# 6_cpu_registers_b.net
KiCad netlist of a schematic drawn in EAGLE
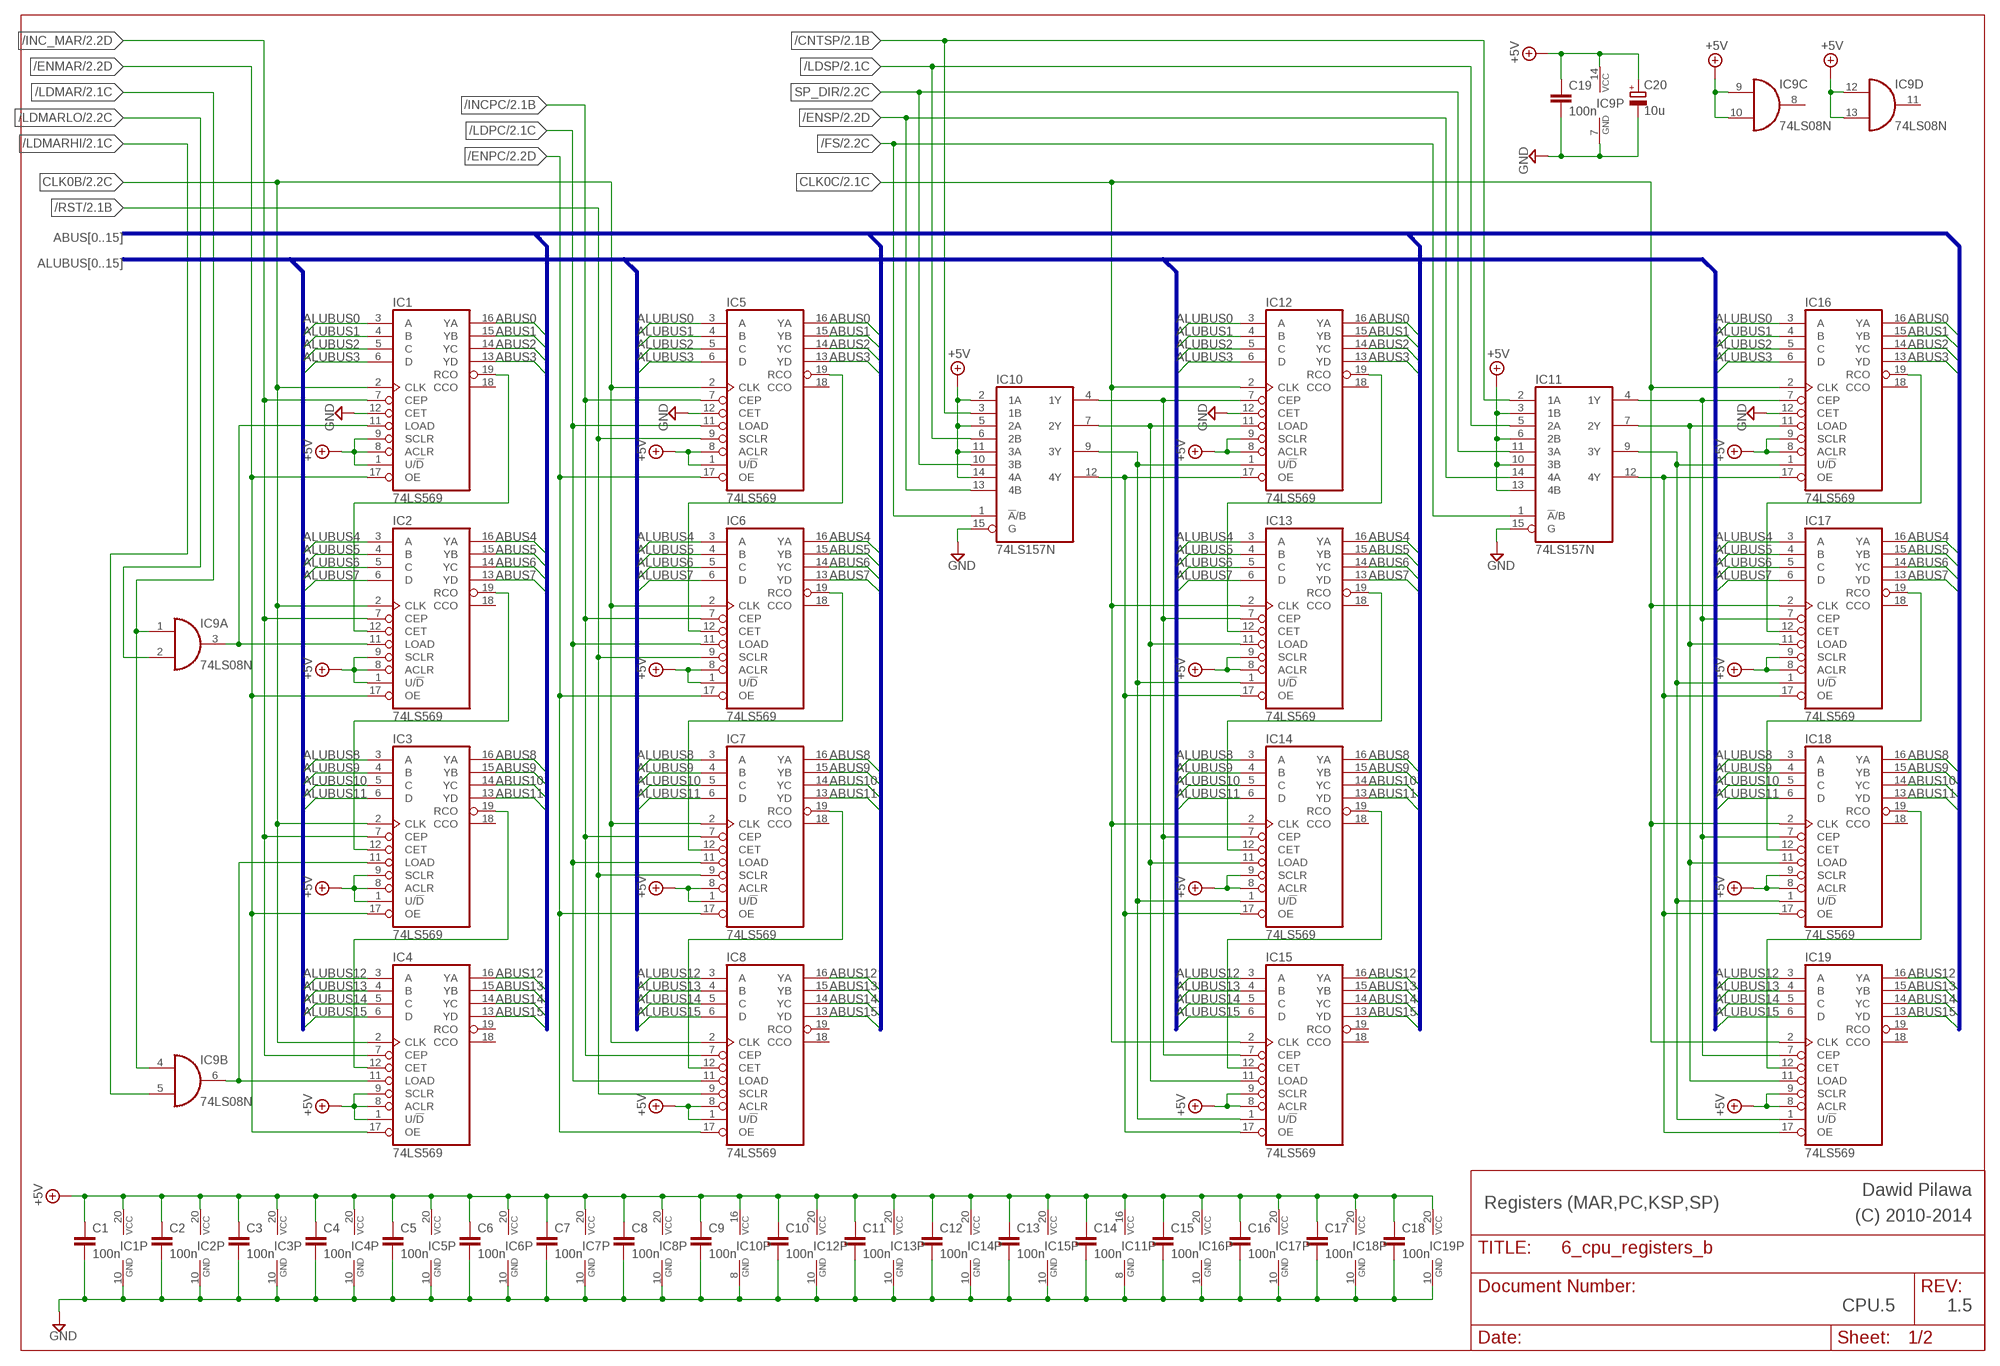
[diagram p0: schematic, sheet 1]
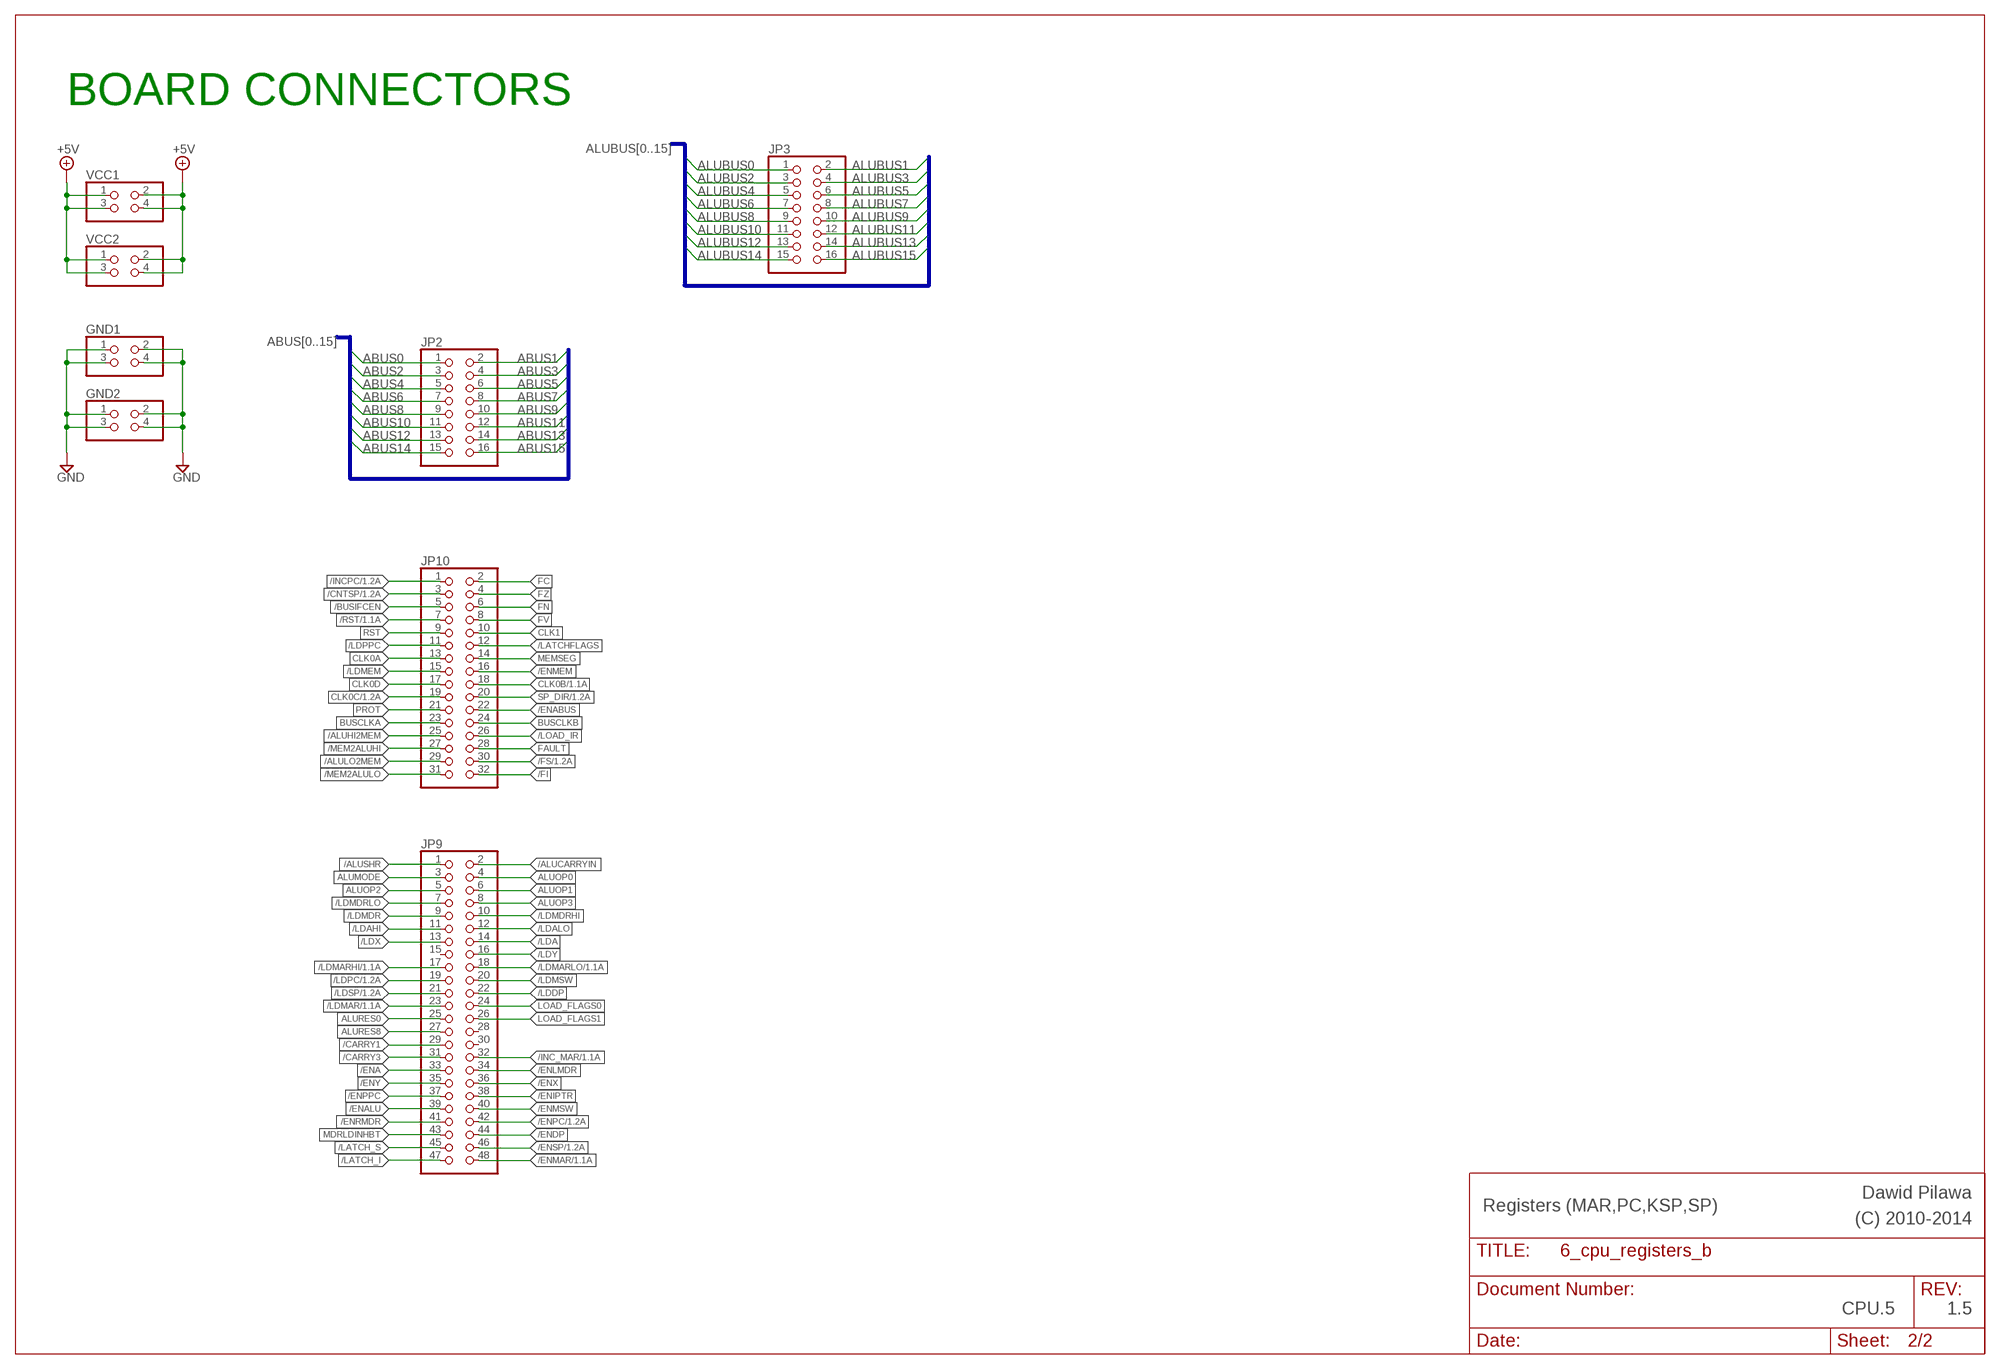
[diagram p1: schematic, sheet 2]

(export (version "E")
  (design (tool "Eeschema 10.0.6"))
  (components
    (comp (ref "GND1")
      (value "PINHD-2X2")
      (footprint "eagle-import:2X02")
      (libsource (lib "eagle-import") (part "PINHD-2X2"))
    )
    (comp (ref "GND2")
      (value "PINHD-2X2")
      (footprint "eagle-import:2X02")
      (libsource (lib "eagle-import") (part "PINHD-2X2"))
    )
    (comp (ref "JP2")
      (value "PINHD-2X8")
      (footprint "eagle-import:2X08")
      (libsource (lib "eagle-import") (part "PINHD-2X8"))
    )
    (comp (ref "JP3")
      (value "PINHD-2X8")
      (footprint "eagle-import:2X08")
      (libsource (lib "eagle-import") (part "PINHD-2X8"))
    )
    (comp (ref "JP9")
      (value "PINHD-2X24")
      (footprint "eagle-import:2X24")
      (libsource (lib "eagle-import") (part "PINHD-2X24"))
    )
    (comp (ref "JP10")
      (value "PINHD-2X16")
      (footprint "eagle-import:2X16")
      (libsource (lib "eagle-import") (part "PINHD-2X16"))
    )
    (comp (ref "VCC1")
      (value "PINHD-2X2")
      (footprint "eagle-import:2X02")
      (libsource (lib "eagle-import") (part "PINHD-2X2"))
    )
    (comp (ref "VCC2")
      (value "PINHD-2X2")
      (footprint "eagle-import:2X02")
      (libsource (lib "eagle-import") (part "PINHD-2X2"))
    )
    (comp (ref "C1")
      (value "100n")
      (footprint "eagle-import:C050-024X044")
      (libsource (lib "eagle-import") (part "C-EU050-024X044"))
    )
    (comp (ref "C2")
      (value "100n")
      (footprint "eagle-import:C050-024X044")
      (libsource (lib "eagle-import") (part "C-EU050-024X044"))
    )
    (comp (ref "C3")
      (value "100n")
      (footprint "eagle-import:C050-024X044")
      (libsource (lib "eagle-import") (part "C-EU050-024X044"))
    )
    (comp (ref "C4")
      (value "100n")
      (footprint "eagle-import:C050-024X044")
      (libsource (lib "eagle-import") (part "C-EU050-024X044"))
    )
    (comp (ref "C5")
      (value "100n")
      (footprint "eagle-import:C050-024X044")
      (libsource (lib "eagle-import") (part "C-EU050-024X044"))
    )
    (comp (ref "C6")
      (value "100n")
      (footprint "eagle-import:C050-024X044")
      (libsource (lib "eagle-import") (part "C-EU050-024X044"))
    )
    (comp (ref "C7")
      (value "100n")
      (footprint "eagle-import:C050-024X044")
      (libsource (lib "eagle-import") (part "C-EU050-024X044"))
    )
    (comp (ref "C8")
      (value "100n")
      (footprint "eagle-import:C050-024X044")
      (libsource (lib "eagle-import") (part "C-EU050-024X044"))
    )
    (comp (ref "C9")
      (value "100n")
      (footprint "eagle-import:C050-024X044")
      (libsource (lib "eagle-import") (part "C-EU050-024X044"))
    )
    (comp (ref "C10")
      (value "100n")
      (footprint "eagle-import:C050-024X044")
      (libsource (lib "eagle-import") (part "C-EU050-024X044"))
    )
    (comp (ref "C11")
      (value "100n")
      (footprint "eagle-import:C050-024X044")
      (libsource (lib "eagle-import") (part "C-EU050-024X044"))
    )
    (comp (ref "C12")
      (value "100n")
      (footprint "eagle-import:C050-024X044")
      (libsource (lib "eagle-import") (part "C-EU050-024X044"))
    )
    (comp (ref "C13")
      (value "100n")
      (footprint "eagle-import:C050-024X044")
      (libsource (lib "eagle-import") (part "C-EU050-024X044"))
    )
    (comp (ref "C14")
      (value "100n")
      (footprint "eagle-import:C050-024X044")
      (libsource (lib "eagle-import") (part "C-EU050-024X044"))
    )
    (comp (ref "C15")
      (value "100n")
      (footprint "eagle-import:C050-024X044")
      (libsource (lib "eagle-import") (part "C-EU050-024X044"))
    )
    (comp (ref "C16")
      (value "100n")
      (footprint "eagle-import:C050-024X044")
      (libsource (lib "eagle-import") (part "C-EU050-024X044"))
    )
    (comp (ref "C17")
      (value "100n")
      (footprint "eagle-import:C050-024X044")
      (libsource (lib "eagle-import") (part "C-EU050-024X044"))
    )
    (comp (ref "C18")
      (value "100n")
      (footprint "eagle-import:C050-024X044")
      (libsource (lib "eagle-import") (part "C-EU050-024X044"))
    )
    (comp (ref "C19")
      (value "100n")
      (footprint "eagle-import:C050-024X044")
      (libsource (lib "eagle-import") (part "C-EU050-024X044"))
    )
    (comp (ref "C20")
      (value "10u")
      (footprint "eagle-import:E2,5-6")
      (libsource (lib "eagle-import") (part "CPOL-EUE2.5-6"))
    )
    (comp (ref "IC1")
      (value "74LS569")
      (footprint "eagle-import:DIL20")
      (libsource (lib "eagle-import") (part "74569LS"))
    )
    (comp (ref "IC2")
      (value "74LS569")
      (footprint "eagle-import:DIL20")
      (libsource (lib "eagle-import") (part "74569LS"))
    )
    (comp (ref "IC3")
      (value "74LS569")
      (footprint "eagle-import:DIL20")
      (libsource (lib "eagle-import") (part "74569LS"))
    )
    (comp (ref "IC4")
      (value "74LS569")
      (footprint "eagle-import:DIL20")
      (libsource (lib "eagle-import") (part "74569LS"))
    )
    (comp (ref "IC5")
      (value "74LS569")
      (footprint "eagle-import:DIL20")
      (libsource (lib "eagle-import") (part "74569LS"))
    )
    (comp (ref "IC6")
      (value "74LS569")
      (footprint "eagle-import:DIL20")
      (libsource (lib "eagle-import") (part "74569LS"))
    )
    (comp (ref "IC7")
      (value "74LS569")
      (footprint "eagle-import:DIL20")
      (libsource (lib "eagle-import") (part "74569LS"))
    )
    (comp (ref "IC8")
      (value "74LS569")
      (footprint "eagle-import:DIL20")
      (libsource (lib "eagle-import") (part "74569LS"))
    )
    (comp (ref "IC9")
      (value "74LS08N")
      (footprint "eagle-import:DIL14")
      (libsource (lib "eagle-import") (part "7408NLS"))
    )
    (comp (ref "IC10")
      (value "74LS157N")
      (footprint "eagle-import:DIL16")
      (libsource (lib "eagle-import") (part "74157NLS"))
    )
    (comp (ref "IC11")
      (value "74LS157N")
      (footprint "eagle-import:DIL16")
      (libsource (lib "eagle-import") (part "74157NLS"))
    )
    (comp (ref "IC12")
      (value "74LS569")
      (footprint "eagle-import:DIL20")
      (libsource (lib "eagle-import") (part "74569LS"))
    )
    (comp (ref "IC13")
      (value "74LS569")
      (footprint "eagle-import:DIL20")
      (libsource (lib "eagle-import") (part "74569LS"))
    )
    (comp (ref "IC14")
      (value "74LS569")
      (footprint "eagle-import:DIL20")
      (libsource (lib "eagle-import") (part "74569LS"))
    )
    (comp (ref "IC15")
      (value "74LS569")
      (footprint "eagle-import:DIL20")
      (libsource (lib "eagle-import") (part "74569LS"))
    )
    (comp (ref "IC16")
      (value "74LS569")
      (footprint "eagle-import:DIL20")
      (libsource (lib "eagle-import") (part "74569LS"))
    )
    (comp (ref "IC17")
      (value "74LS569")
      (footprint "eagle-import:DIL20")
      (libsource (lib "eagle-import") (part "74569LS"))
    )
    (comp (ref "IC18")
      (value "74LS569")
      (footprint "eagle-import:DIL20")
      (libsource (lib "eagle-import") (part "74569LS"))
    )
    (comp (ref "IC19")
      (value "74LS569")
      (footprint "eagle-import:DIL20")
      (libsource (lib "eagle-import") (part "74569LS"))
    )
  )
  (nets
    (net (code "1") (name "+5V") (class "Default")
      (node (ref "C1") (pin "1") (pinfunction "1_1") (pintype "passive"))
      (node (ref "C10") (pin "1") (pinfunction "1_1") (pintype "passive"))
      (node (ref "C11") (pin "1") (pinfunction "1_1") (pintype "passive"))
      (node (ref "C12") (pin "1") (pinfunction "1_1") (pintype "passive"))
      (node (ref "C13") (pin "1") (pinfunction "1_1") (pintype "passive"))
      (node (ref "C14") (pin "1") (pinfunction "1_1") (pintype "passive"))
      (node (ref "C15") (pin "1") (pinfunction "1_1") (pintype "passive"))
      (node (ref "C16") (pin "1") (pinfunction "1_1") (pintype "passive"))
      (node (ref "C17") (pin "1") (pinfunction "1_1") (pintype "passive"))
      (node (ref "C18") (pin "1") (pinfunction "1_1") (pintype "passive"))
      (node (ref "C19") (pin "1") (pinfunction "1_1") (pintype "passive"))
      (node (ref "C2") (pin "1") (pinfunction "1_1") (pintype "passive"))
      (node (ref "C20") (pin "+") (pinfunction "+_+") (pintype "passive"))
      (node (ref "C3") (pin "1") (pinfunction "1_1") (pintype "passive"))
      (node (ref "C4") (pin "1") (pinfunction "1_1") (pintype "passive"))
      (node (ref "C5") (pin "1") (pinfunction "1_1") (pintype "passive"))
      (node (ref "C6") (pin "1") (pinfunction "1_1") (pintype "passive"))
      (node (ref "C7") (pin "1") (pinfunction "1_1") (pintype "passive"))
      (node (ref "C8") (pin "1") (pinfunction "1_1") (pintype "passive"))
      (node (ref "C9") (pin "1") (pinfunction "1_1") (pintype "passive"))
      (node (ref "IC1") (pin "1") (pinfunction "U/~{D}_1") (pintype "input"))
      (node (ref "IC1") (pin "20") (pinfunction "VCC_20") (pintype "power_in"))
      (node (ref "IC1") (pin "8") (pinfunction "ACLR_8") (pintype "input"))
      (node (ref "IC1") (pin "9") (pinfunction "SCLR_9") (pintype "input"))
      (node (ref "IC10") (pin "11") (pinfunction "3A_11") (pintype "input"))
      (node (ref "IC10") (pin "14") (pinfunction "4A_14") (pintype "input"))
      (node (ref "IC10") (pin "16") (pinfunction "VCC_16") (pintype "power_in"))
      (node (ref "IC10") (pin "2") (pinfunction "1A_2") (pintype "input"))
      (node (ref "IC10") (pin "5") (pinfunction "2A_5") (pintype "input"))
      (node (ref "IC11") (pin "10") (pinfunction "3B_10") (pintype "input"))
      (node (ref "IC11") (pin "13") (pinfunction "4B_13") (pintype "input"))
      (node (ref "IC11") (pin "16") (pinfunction "VCC_16") (pintype "power_in"))
      (node (ref "IC11") (pin "3") (pinfunction "1B_3") (pintype "input"))
      (node (ref "IC11") (pin "6") (pinfunction "2B_6") (pintype "input"))
      (node (ref "IC12") (pin "20") (pinfunction "VCC_20") (pintype "power_in"))
      (node (ref "IC12") (pin "8") (pinfunction "ACLR_8") (pintype "input"))
      (node (ref "IC12") (pin "9") (pinfunction "SCLR_9") (pintype "input"))
      (node (ref "IC13") (pin "20") (pinfunction "VCC_20") (pintype "power_in"))
      (node (ref "IC13") (pin "8") (pinfunction "ACLR_8") (pintype "input"))
      (node (ref "IC13") (pin "9") (pinfunction "SCLR_9") (pintype "input"))
      (node (ref "IC14") (pin "20") (pinfunction "VCC_20") (pintype "power_in"))
      (node (ref "IC14") (pin "8") (pinfunction "ACLR_8") (pintype "input"))
      (node (ref "IC14") (pin "9") (pinfunction "SCLR_9") (pintype "input"))
      (node (ref "IC15") (pin "20") (pinfunction "VCC_20") (pintype "power_in"))
      (node (ref "IC15") (pin "8") (pinfunction "ACLR_8") (pintype "input"))
      (node (ref "IC15") (pin "9") (pinfunction "SCLR_9") (pintype "input"))
      (node (ref "IC16") (pin "20") (pinfunction "VCC_20") (pintype "power_in"))
      (node (ref "IC16") (pin "8") (pinfunction "ACLR_8") (pintype "input"))
      (node (ref "IC16") (pin "9") (pinfunction "SCLR_9") (pintype "input"))
      (node (ref "IC17") (pin "20") (pinfunction "VCC_20") (pintype "power_in"))
      (node (ref "IC17") (pin "8") (pinfunction "ACLR_8") (pintype "input"))
      (node (ref "IC17") (pin "9") (pinfunction "SCLR_9") (pintype "input"))
      (node (ref "IC18") (pin "20") (pinfunction "VCC_20") (pintype "power_in"))
      (node (ref "IC18") (pin "8") (pinfunction "ACLR_8") (pintype "input"))
      (node (ref "IC18") (pin "9") (pinfunction "SCLR_9") (pintype "input"))
      (node (ref "IC19") (pin "20") (pinfunction "VCC_20") (pintype "power_in"))
      (node (ref "IC19") (pin "8") (pinfunction "ACLR_8") (pintype "input"))
      (node (ref "IC19") (pin "9") (pinfunction "SCLR_9") (pintype "input"))
      (node (ref "IC2") (pin "1") (pinfunction "U/~{D}_1") (pintype "input"))
      (node (ref "IC2") (pin "20") (pinfunction "VCC_20") (pintype "power_in"))
      (node (ref "IC2") (pin "8") (pinfunction "ACLR_8") (pintype "input"))
      (node (ref "IC2") (pin "9") (pinfunction "SCLR_9") (pintype "input"))
      (node (ref "IC3") (pin "1") (pinfunction "U/~{D}_1") (pintype "input"))
      (node (ref "IC3") (pin "20") (pinfunction "VCC_20") (pintype "power_in"))
      (node (ref "IC3") (pin "8") (pinfunction "ACLR_8") (pintype "input"))
      (node (ref "IC3") (pin "9") (pinfunction "SCLR_9") (pintype "input"))
      (node (ref "IC4") (pin "1") (pinfunction "U/~{D}_1") (pintype "input"))
      (node (ref "IC4") (pin "20") (pinfunction "VCC_20") (pintype "power_in"))
      (node (ref "IC4") (pin "8") (pinfunction "ACLR_8") (pintype "input"))
      (node (ref "IC4") (pin "9") (pinfunction "SCLR_9") (pintype "input"))
      (node (ref "IC5") (pin "1") (pinfunction "U/~{D}_1") (pintype "input"))
      (node (ref "IC5") (pin "20") (pinfunction "VCC_20") (pintype "power_in"))
      (node (ref "IC5") (pin "8") (pinfunction "ACLR_8") (pintype "input"))
      (node (ref "IC6") (pin "1") (pinfunction "U/~{D}_1") (pintype "input"))
      (node (ref "IC6") (pin "20") (pinfunction "VCC_20") (pintype "power_in"))
      (node (ref "IC6") (pin "8") (pinfunction "ACLR_8") (pintype "input"))
      (node (ref "IC7") (pin "1") (pinfunction "U/~{D}_1") (pintype "input"))
      (node (ref "IC7") (pin "20") (pinfunction "VCC_20") (pintype "power_in"))
      (node (ref "IC7") (pin "8") (pinfunction "ACLR_8") (pintype "input"))
      (node (ref "IC8") (pin "1") (pinfunction "U/~{D}_1") (pintype "input"))
      (node (ref "IC8") (pin "20") (pinfunction "VCC_20") (pintype "power_in"))
      (node (ref "IC8") (pin "8") (pinfunction "ACLR_8") (pintype "input"))
      (node (ref "IC9") (pin "10") (pinfunction "I1_10") (pintype "input"))
      (node (ref "IC9") (pin "12") (pinfunction "I0_12") (pintype "input"))
      (node (ref "IC9") (pin "13") (pinfunction "I1_13") (pintype "input"))
      (node (ref "IC9") (pin "14") (pinfunction "VCC_14") (pintype "power_in"))
      (node (ref "IC9") (pin "9") (pinfunction "I0_9") (pintype "input"))
      (node (ref "VCC1") (pin "1") (pinfunction "1_1") (pintype "passive"))
      (node (ref "VCC1") (pin "2") (pinfunction "2_2") (pintype "passive"))
      (node (ref "VCC1") (pin "3") (pinfunction "3_3") (pintype "passive"))
      (node (ref "VCC1") (pin "4") (pinfunction "4_4") (pintype "passive"))
      (node (ref "VCC2") (pin "1") (pinfunction "1_1") (pintype "passive"))
      (node (ref "VCC2") (pin "2") (pinfunction "2_2") (pintype "passive"))
      (node (ref "VCC2") (pin "3") (pinfunction "3_3") (pintype "passive"))
      (node (ref "VCC2") (pin "4") (pinfunction "4_4") (pintype "passive"))
    )
    (net (code "6") (name "ABUS0") (class "Default")
      (node (ref "IC1") (pin "16") (pinfunction "YA_16") (pintype "open_collector"))
      (node (ref "IC12") (pin "16") (pinfunction "YA_16") (pintype "open_collector"))
      (node (ref "IC16") (pin "16") (pinfunction "YA_16") (pintype "open_collector"))
      (node (ref "IC5") (pin "16") (pinfunction "YA_16") (pintype "open_collector"))
      (node (ref "JP2") (pin "1") (pinfunction "1_1") (pintype "passive"))
    )
    (net (code "7") (name "ABUS1") (class "Default")
      (node (ref "IC1") (pin "15") (pinfunction "YB_15") (pintype "open_collector"))
      (node (ref "IC12") (pin "15") (pinfunction "YB_15") (pintype "open_collector"))
      (node (ref "IC16") (pin "15") (pinfunction "YB_15") (pintype "open_collector"))
      (node (ref "IC5") (pin "15") (pinfunction "YB_15") (pintype "open_collector"))
      (node (ref "JP2") (pin "2") (pinfunction "2_2") (pintype "passive"))
    )
    (net (code "8") (name "ABUS2") (class "Default")
      (node (ref "IC1") (pin "14") (pinfunction "YC_14") (pintype "open_collector"))
      (node (ref "IC12") (pin "14") (pinfunction "YC_14") (pintype "open_collector"))
      (node (ref "IC16") (pin "14") (pinfunction "YC_14") (pintype "open_collector"))
      (node (ref "IC5") (pin "14") (pinfunction "YC_14") (pintype "open_collector"))
      (node (ref "JP2") (pin "3") (pinfunction "3_3") (pintype "passive"))
    )
    (net (code "9") (name "ABUS3") (class "Default")
      (node (ref "IC1") (pin "13") (pinfunction "YD_13") (pintype "open_collector"))
      (node (ref "IC12") (pin "13") (pinfunction "YD_13") (pintype "open_collector"))
      (node (ref "IC16") (pin "13") (pinfunction "YD_13") (pintype "open_collector"))
      (node (ref "IC5") (pin "13") (pinfunction "YD_13") (pintype "open_collector"))
      (node (ref "JP2") (pin "4") (pinfunction "4_4") (pintype "passive"))
    )
    (net (code "10") (name "ABUS4") (class "Default")
      (node (ref "IC13") (pin "16") (pinfunction "YA_16") (pintype "open_collector"))
      (node (ref "IC17") (pin "16") (pinfunction "YA_16") (pintype "open_collector"))
      (node (ref "IC2") (pin "16") (pinfunction "YA_16") (pintype "open_collector"))
      (node (ref "IC6") (pin "16") (pinfunction "YA_16") (pintype "open_collector"))
      (node (ref "JP2") (pin "5") (pinfunction "5_5") (pintype "passive"))
    )
    (net (code "11") (name "ABUS5") (class "Default")
      (node (ref "IC13") (pin "15") (pinfunction "YB_15") (pintype "open_collector"))
      (node (ref "IC17") (pin "15") (pinfunction "YB_15") (pintype "open_collector"))
      (node (ref "IC2") (pin "15") (pinfunction "YB_15") (pintype "open_collector"))
      (node (ref "IC6") (pin "15") (pinfunction "YB_15") (pintype "open_collector"))
      (node (ref "JP2") (pin "6") (pinfunction "6_6") (pintype "passive"))
    )
    (net (code "12") (name "ABUS6") (class "Default")
      (node (ref "IC13") (pin "14") (pinfunction "YC_14") (pintype "open_collector"))
      (node (ref "IC17") (pin "14") (pinfunction "YC_14") (pintype "open_collector"))
      (node (ref "IC2") (pin "14") (pinfunction "YC_14") (pintype "open_collector"))
      (node (ref "IC6") (pin "14") (pinfunction "YC_14") (pintype "open_collector"))
      (node (ref "JP2") (pin "7") (pinfunction "7_7") (pintype "passive"))
    )
    (net (code "13") (name "ABUS7") (class "Default")
      (node (ref "IC13") (pin "13") (pinfunction "YD_13") (pintype "open_collector"))
      (node (ref "IC17") (pin "13") (pinfunction "YD_13") (pintype "open_collector"))
      (node (ref "IC2") (pin "13") (pinfunction "YD_13") (pintype "open_collector"))
      (node (ref "IC6") (pin "13") (pinfunction "YD_13") (pintype "open_collector"))
      (node (ref "JP2") (pin "8") (pinfunction "8_8") (pintype "passive"))
    )
    (net (code "14") (name "ABUS8") (class "Default")
      (node (ref "IC14") (pin "16") (pinfunction "YA_16") (pintype "open_collector"))
      (node (ref "IC18") (pin "16") (pinfunction "YA_16") (pintype "open_collector"))
      (node (ref "IC3") (pin "16") (pinfunction "YA_16") (pintype "open_collector"))
      (node (ref "IC7") (pin "16") (pinfunction "YA_16") (pintype "open_collector"))
      (node (ref "JP2") (pin "9") (pinfunction "9_9") (pintype "passive"))
    )
    (net (code "15") (name "ABUS9") (class "Default")
      (node (ref "IC14") (pin "15") (pinfunction "YB_15") (pintype "open_collector"))
      (node (ref "IC18") (pin "15") (pinfunction "YB_15") (pintype "open_collector"))
      (node (ref "IC3") (pin "15") (pinfunction "YB_15") (pintype "open_collector"))
      (node (ref "IC7") (pin "15") (pinfunction "YB_15") (pintype "open_collector"))
      (node (ref "JP2") (pin "10") (pinfunction "10_10") (pintype "passive"))
    )
    (net (code "16") (name "ABUS10") (class "Default")
      (node (ref "IC14") (pin "14") (pinfunction "YC_14") (pintype "open_collector"))
      (node (ref "IC18") (pin "14") (pinfunction "YC_14") (pintype "open_collector"))
      (node (ref "IC3") (pin "14") (pinfunction "YC_14") (pintype "open_collector"))
      (node (ref "IC7") (pin "14") (pinfunction "YC_14") (pintype "open_collector"))
      (node (ref "JP2") (pin "11") (pinfunction "11_11") (pintype "passive"))
    )
    (net (code "17") (name "ABUS11") (class "Default")
      (node (ref "IC14") (pin "13") (pinfunction "YD_13") (pintype "open_collector"))
      (node (ref "IC18") (pin "13") (pinfunction "YD_13") (pintype "open_collector"))
      (node (ref "IC3") (pin "13") (pinfunction "YD_13") (pintype "open_collector"))
      (node (ref "IC7") (pin "13") (pinfunction "YD_13") (pintype "open_collector"))
      (node (ref "JP2") (pin "12") (pinfunction "12_12") (pintype "passive"))
    )
    (net (code "18") (name "ABUS12") (class "Default")
      (node (ref "IC15") (pin "16") (pinfunction "YA_16") (pintype "open_collector"))
      (node (ref "IC19") (pin "16") (pinfunction "YA_16") (pintype "open_collector"))
      (node (ref "IC4") (pin "16") (pinfunction "YA_16") (pintype "open_collector"))
      (node (ref "IC8") (pin "16") (pinfunction "YA_16") (pintype "open_collector"))
      (node (ref "JP2") (pin "13") (pinfunction "13_13") (pintype "passive"))
    )
    (net (code "19") (name "ABUS13") (class "Default")
      (node (ref "IC15") (pin "15") (pinfunction "YB_15") (pintype "open_collector"))
      (node (ref "IC19") (pin "15") (pinfunction "YB_15") (pintype "open_collector"))
      (node (ref "IC4") (pin "15") (pinfunction "YB_15") (pintype "open_collector"))
      (node (ref "IC8") (pin "15") (pinfunction "YB_15") (pintype "open_collector"))
      (node (ref "JP2") (pin "14") (pinfunction "14_14") (pintype "passive"))
    )
    (net (code "20") (name "ABUS14") (class "Default")
      (node (ref "IC15") (pin "14") (pinfunction "YC_14") (pintype "open_collector"))
      (node (ref "IC19") (pin "14") (pinfunction "YC_14") (pintype "open_collector"))
      (node (ref "IC4") (pin "14") (pinfunction "YC_14") (pintype "open_collector"))
      (node (ref "IC8") (pin "14") (pinfunction "YC_14") (pintype "open_collector"))
      (node (ref "JP2") (pin "15") (pinfunction "15_15") (pintype "passive"))
    )
    (net (code "21") (name "ABUS15") (class "Default")
      (node (ref "IC15") (pin "13") (pinfunction "YD_13") (pintype "open_collector"))
      (node (ref "IC19") (pin "13") (pinfunction "YD_13") (pintype "open_collector"))
      (node (ref "IC4") (pin "13") (pinfunction "YD_13") (pintype "open_collector"))
      (node (ref "IC8") (pin "13") (pinfunction "YD_13") (pintype "open_collector"))
      (node (ref "JP2") (pin "16") (pinfunction "16_16") (pintype "passive"))
    )
    (net (code "22") (name "ALUBUS0") (class "Default")
      (node (ref "IC1") (pin "3") (pinfunction "A_3") (pintype "input"))
      (node (ref "IC12") (pin "3") (pinfunction "A_3") (pintype "input"))
      (node (ref "IC16") (pin "3") (pinfunction "A_3") (pintype "input"))
      (node (ref "IC5") (pin "3") (pinfunction "A_3") (pintype "input"))
      (node (ref "JP3") (pin "1") (pinfunction "1_1") (pintype "passive"))
    )
    (net (code "23") (name "ALUBUS1") (class "Default")
      (node (ref "IC1") (pin "4") (pinfunction "B_4") (pintype "input"))
      (node (ref "IC12") (pin "4") (pinfunction "B_4") (pintype "input"))
      (node (ref "IC16") (pin "4") (pinfunction "B_4") (pintype "input"))
      (node (ref "IC5") (pin "4") (pinfunction "B_4") (pintype "input"))
      (node (ref "JP3") (pin "2") (pinfunction "2_2") (pintype "passive"))
    )
    (net (code "24") (name "ALUBUS2") (class "Default")
      (node (ref "IC1") (pin "5") (pinfunction "C_5") (pintype "input"))
      (node (ref "IC12") (pin "5") (pinfunction "C_5") (pintype "input"))
      (node (ref "IC16") (pin "5") (pinfunction "C_5") (pintype "input"))
      (node (ref "IC5") (pin "5") (pinfunction "C_5") (pintype "input"))
      (node (ref "JP3") (pin "3") (pinfunction "3_3") (pintype "passive"))
    )
    (net (code "25") (name "ALUBUS3") (class "Default")
      (node (ref "IC1") (pin "6") (pinfunction "D_6") (pintype "input"))
      (node (ref "IC12") (pin "6") (pinfunction "D_6") (pintype "input"))
      (node (ref "IC16") (pin "6") (pinfunction "D_6") (pintype "input"))
      (node (ref "IC5") (pin "6") (pinfunction "D_6") (pintype "input"))
      (node (ref "JP3") (pin "4") (pinfunction "4_4") (pintype "passive"))
    )
    (net (code "26") (name "ALUBUS4") (class "Default")
      (node (ref "IC13") (pin "3") (pinfunction "A_3") (pintype "input"))
      (node (ref "IC17") (pin "3") (pinfunction "A_3") (pintype "input"))
      (node (ref "IC2") (pin "3") (pinfunction "A_3") (pintype "input"))
      (node (ref "IC6") (pin "3") (pinfunction "A_3") (pintype "input"))
      (node (ref "JP3") (pin "5") (pinfunction "5_5") (pintype "passive"))
    )
    (net (code "27") (name "ALUBUS5") (class "Default")
      (node (ref "IC13") (pin "4") (pinfunction "B_4") (pintype "input"))
      (node (ref "IC17") (pin "4") (pinfunction "B_4") (pintype "input"))
      (node (ref "IC2") (pin "4") (pinfunction "B_4") (pintype "input"))
      (node (ref "IC6") (pin "4") (pinfunction "B_4") (pintype "input"))
      (node (ref "JP3") (pin "6") (pinfunction "6_6") (pintype "passive"))
    )
    (net (code "28") (name "ALUBUS6") (class "Default")
      (node (ref "IC13") (pin "5") (pinfunction "C_5") (pintype "input"))
      (node (ref "IC17") (pin "5") (pinfunction "C_5") (pintype "input"))
      (node (ref "IC2") (pin "5") (pinfunction "C_5") (pintype "input"))
      (node (ref "IC6") (pin "5") (pinfunction "C_5") (pintype "input"))
      (node (ref "JP3") (pin "7") (pinfunction "7_7") (pintype "passive"))
    )
    (net (code "29") (name "ALUBUS7") (class "Default")
      (node (ref "IC13") (pin "6") (pinfunction "D_6") (pintype "input"))
      (node (ref "IC17") (pin "6") (pinfunction "D_6") (pintype "input"))
      (node (ref "IC2") (pin "6") (pinfunction "D_6") (pintype "input"))
      (node (ref "IC6") (pin "6") (pinfunction "D_6") (pintype "input"))
      (node (ref "JP3") (pin "8") (pinfunction "8_8") (pintype "passive"))
    )
    (net (code "30") (name "ALUBUS8") (class "Default")
      (node (ref "IC14") (pin "3") (pinfunction "A_3") (pintype "input"))
      (node (ref "IC18") (pin "3") (pinfunction "A_3") (pintype "input"))
      (node (ref "IC3") (pin "3") (pinfunction "A_3") (pintype "input"))
      (node (ref "IC7") (pin "3") (pinfunction "A_3") (pintype "input"))
      (node (ref "JP3") (pin "9") (pinfunction "9_9") (pintype "passive"))
    )
    (net (code "31") (name "ALUBUS9") (class "Default")
      (node (ref "IC14") (pin "4") (pinfunction "B_4") (pintype "input"))
      (node (ref "IC18") (pin "4") (pinfunction "B_4") (pintype "input"))
      (node (ref "IC3") (pin "4") (pinfunction "B_4") (pintype "input"))
      (node (ref "IC7") (pin "4") (pinfunction "B_4") (pintype "input"))
      (node (ref "JP3") (pin "10") (pinfunction "10_10") (pintype "passive"))
    )
    (net (code "32") (name "ALUBUS10") (class "Default")
      (node (ref "IC14") (pin "5") (pinfunction "C_5") (pintype "input"))
      (node (ref "IC18") (pin "5") (pinfunction "C_5") (pintype "input"))
      (node (ref "IC3") (pin "5") (pinfunction "C_5") (pintype "input"))
      (node (ref "IC7") (pin "5") (pinfunction "C_5") (pintype "input"))
      (node (ref "JP3") (pin "11") (pinfunction "11_11") (pintype "passive"))
    )
    (net (code "33") (name "ALUBUS11") (class "Default")
      (node (ref "IC14") (pin "6") (pinfunction "D_6") (pintype "input"))
      (node (ref "IC18") (pin "6") (pinfunction "D_6") (pintype "input"))
      (node (ref "IC3") (pin "6") (pinfunction "D_6") (pintype "input"))
      (node (ref "IC7") (pin "6") (pinfunction "D_6") (pintype "input"))
      (node (ref "JP3") (pin "12") (pinfunction "12_12") (pintype "passive"))
    )
    (net (code "34") (name "ALUBUS12") (class "Default")
      (node (ref "IC15") (pin "3") (pinfunction "A_3") (pintype "input"))
      (node (ref "IC19") (pin "3") (pinfunction "A_3") (pintype "input"))
      (node (ref "IC4") (pin "3") (pinfunction "A_3") (pintype "input"))
      (node (ref "IC8") (pin "3") (pinfunction "A_3") (pintype "input"))
      (node (ref "JP3") (pin "13") (pinfunction "13_13") (pintype "passive"))
    )
    (net (code "35") (name "ALUBUS13") (class "Default")
      (node (ref "IC15") (pin "4") (pinfunction "B_4") (pintype "input"))
      (node (ref "IC19") (pin "4") (pinfunction "B_4") (pintype "input"))
      (node (ref "IC4") (pin "4") (pinfunction "B_4") (pintype "input"))
      (node (ref "IC8") (pin "4") (pinfunction "B_4") (pintype "input"))
      (node (ref "JP3") (pin "14") (pinfunction "14_14") (pintype "passive"))
    )
    (net (code "36") (name "ALUBUS14") (class "Default")
      (node (ref "IC15") (pin "5") (pinfunction "C_5") (pintype "input"))
      (node (ref "IC19") (pin "5") (pinfunction "C_5") (pintype "input"))
      (node (ref "IC4") (pin "5") (pinfunction "C_5") (pintype "input"))
      (node (ref "IC8") (pin "5") (pinfunction "C_5") (pintype "input"))
      (node (ref "JP3") (pin "15") (pinfunction "15_15") (pintype "passive"))
    )
    (net (code "37") (name "ALUBUS15") (class "Default")
      (node (ref "IC15") (pin "6") (pinfunction "D_6") (pintype "input"))
      (node (ref "IC19") (pin "6") (pinfunction "D_6") (pintype "input"))
      (node (ref "IC4") (pin "6") (pinfunction "D_6") (pintype "input"))
      (node (ref "IC8") (pin "6") (pinfunction "D_6") (pintype "input"))
      (node (ref "JP3") (pin "16") (pinfunction "16_16") (pintype "passive"))
    )
    (net (code "38") (name "ALUMODE") (class "Default")
      (node (ref "JP9") (pin "3") (pinfunction "3_3") (pintype "passive"))
    )
    (net (code "39") (name "ALUOP0") (class "Default")
      (node (ref "JP9") (pin "4") (pinfunction "4_4") (pintype "passive"))
    )
    (net (code "40") (name "ALUOP1") (class "Default")
      (node (ref "JP9") (pin "6") (pinfunction "6_6") (pintype "passive"))
    )
    (net (code "41") (name "ALUOP2") (class "Default")
      (node (ref "JP9") (pin "5") (pinfunction "5_5") (pintype "passive"))
    )
    (net (code "42") (name "ALUOP3") (class "Default")
      (node (ref "JP9") (pin "8") (pinfunction "8_8") (pintype "passive"))
    )
    (net (code "43") (name "ALURES0") (class "Default")
      (node (ref "JP9") (pin "25") (pinfunction "25_25") (pintype "passive"))
    )
    (net (code "44") (name "ALURES8") (class "Default")
      (node (ref "JP9") (pin "27") (pinfunction "27_27") (pintype "passive"))
    )
    (net (code "45") (name "BUSCLKA") (class "Default")
      (node (ref "JP10") (pin "23") (pinfunction "23_23") (pintype "passive"))
    )
    (net (code "46") (name "BUSCLKB") (class "Default")
      (node (ref "JP10") (pin "24") (pinfunction "24_24") (pintype "passive"))
    )
    (net (code "47") (name "CLK0A") (class "Default")
      (node (ref "JP10") (pin "13") (pinfunction "13_13") (pintype "passive"))
    )
    (net (code "48") (name "CLK0B") (class "Default")
      (node (ref "IC1") (pin "2") (pinfunction "CLK_2") (pintype "input"))
      (node (ref "IC2") (pin "2") (pinfunction "CLK_2") (pintype "input"))
      (node (ref "IC3") (pin "2") (pinfunction "CLK_2") (pintype "input"))
      (node (ref "IC4") (pin "2") (pinfunction "CLK_2") (pintype "input"))
      (node (ref "IC5") (pin "2") (pinfunction "CLK_2") (pintype "input"))
      (node (ref "IC6") (pin "2") (pinfunction "CLK_2") (pintype "input"))
      (node (ref "IC7") (pin "2") (pinfunction "CLK_2") (pintype "input"))
      (node (ref "IC8") (pin "2") (pinfunction "CLK_2") (pintype "input"))
      (node (ref "JP10") (pin "18") (pinfunction "18_18") (pintype "passive"))
    )
    (net (code "49") (name "CLK0C") (class "Default")
      (node (ref "IC12") (pin "2") (pinfunction "CLK_2") (pintype "input"))
      (node (ref "IC13") (pin "2") (pinfunction "CLK_2") (pintype "input"))
      (node (ref "IC14") (pin "2") (pinfunction "CLK_2") (pintype "input"))
      (node (ref "IC15") (pin "2") (pinfunction "CLK_2") (pintype "input"))
      (node (ref "IC16") (pin "2") (pinfunction "CLK_2") (pintype "input"))
      (node (ref "IC17") (pin "2") (pinfunction "CLK_2") (pintype "input"))
      (node (ref "IC18") (pin "2") (pinfunction "CLK_2") (pintype "input"))
      (node (ref "IC19") (pin "2") (pinfunction "CLK_2") (pintype "input"))
      (node (ref "JP10") (pin "19") (pinfunction "19_19") (pintype "passive"))
    )
    (net (code "50") (name "CLK0D") (class "Default")
      (node (ref "JP10") (pin "17") (pinfunction "17_17") (pintype "passive"))
    )
    (net (code "51") (name "CLK1") (class "Default")
      (node (ref "JP10") (pin "10") (pinfunction "10_10") (pintype "passive"))
    )
    (net (code "52") (name "FAULT") (class "Default")
      (node (ref "JP10") (pin "28") (pinfunction "28_28") (pintype "passive"))
    )
    (net (code "53") (name "FC") (class "Default")
      (node (ref "JP10") (pin "2") (pinfunction "2_2") (pintype "passive"))
    )
    (net (code "54") (name "FN") (class "Default")
      (node (ref "JP10") (pin "6") (pinfunction "6_6") (pintype "passive"))
    )
    (net (code "55") (name "FV") (class "Default")
      (node (ref "JP10") (pin "8") (pinfunction "8_8") (pintype "passive"))
    )
    (net (code "56") (name "FZ") (class "Default")
      (node (ref "JP10") (pin "4") (pinfunction "4_4") (pintype "passive"))
    )
    (net (code "57") (name "GND") (class "Default")
      (node (ref "C1") (pin "2") (pinfunction "2_2") (pintype "passive"))
      (node (ref "C10") (pin "2") (pinfunction "2_2") (pintype "passive"))
      (node (ref "C11") (pin "2") (pinfunction "2_2") (pintype "passive"))
      (node (ref "C12") (pin "2") (pinfunction "2_2") (pintype "passive"))
      (node (ref "C13") (pin "2") (pinfunction "2_2") (pintype "passive"))
      (node (ref "C14") (pin "2") (pinfunction "2_2") (pintype "passive"))
      (node (ref "C15") (pin "2") (pinfunction "2_2") (pintype "passive"))
      (node (ref "C16") (pin "2") (pinfunction "2_2") (pintype "passive"))
      (node (ref "C17") (pin "2") (pinfunction "2_2") (pintype "passive"))
      (node (ref "C18") (pin "2") (pinfunction "2_2") (pintype "passive"))
      (node (ref "C19") (pin "2") (pinfunction "2_2") (pintype "passive"))
      (node (ref "C2") (pin "2") (pinfunction "2_2") (pintype "passive"))
      (node (ref "C20") (pin "-") (pinfunction "-_-") (pintype "passive"))
      (node (ref "C3") (pin "2") (pinfunction "2_2") (pintype "passive"))
      (node (ref "C4") (pin "2") (pinfunction "2_2") (pintype "passive"))
      (node (ref "C5") (pin "2") (pinfunction "2_2") (pintype "passive"))
      (node (ref "C6") (pin "2") (pinfunction "2_2") (pintype "passive"))
      (node (ref "C7") (pin "2") (pinfunction "2_2") (pintype "passive"))
      (node (ref "C8") (pin "2") (pinfunction "2_2") (pintype "passive"))
      (node (ref "C9") (pin "2") (pinfunction "2_2") (pintype "passive"))
      (node (ref "GND1") (pin "1") (pinfunction "1_1") (pintype "passive"))
      (node (ref "GND1") (pin "2") (pinfunction "2_2") (pintype "passive"))
      (node (ref "GND1") (pin "3") (pinfunction "3_3") (pintype "passive"))
      (node (ref "GND1") (pin "4") (pinfunction "4_4") (pintype "passive"))
      (node (ref "GND2") (pin "1") (pinfunction "1_1") (pintype "passive"))
      (node (ref "GND2") (pin "2") (pinfunction "2_2") (pintype "passive"))
      (node (ref "GND2") (pin "3") (pinfunction "3_3") (pintype "passive"))
      (node (ref "GND2") (pin "4") (pinfunction "4_4") (pintype "passive"))
      (node (ref "IC1") (pin "10") (pinfunction "GND_10") (pintype "power_in"))
      (node (ref "IC1") (pin "12") (pinfunction "CET_12") (pintype "input"))
      (node (ref "IC10") (pin "15") (pinfunction "G_15") (pintype "input"))
      (node (ref "IC10") (pin "8") (pinfunction "GND_8") (pintype "power_in"))
      (node (ref "IC11") (pin "15") (pinfunction "G_15") (pintype "input"))
      (node (ref "IC11") (pin "8") (pinfunction "GND_8") (pintype "power_in"))
      (node (ref "IC12") (pin "10") (pinfunction "GND_10") (pintype "power_in"))
      (node (ref "IC12") (pin "12") (pinfunction "CET_12") (pintype "input"))
      (node (ref "IC13") (pin "10") (pinfunction "GND_10") (pintype "power_in"))
      (node (ref "IC14") (pin "10") (pinfunction "GND_10") (pintype "power_in"))
      (node (ref "IC15") (pin "10") (pinfunction "GND_10") (pintype "power_in"))
      (node (ref "IC16") (pin "10") (pinfunction "GND_10") (pintype "power_in"))
      (node (ref "IC16") (pin "12") (pinfunction "CET_12") (pintype "input"))
      (node (ref "IC17") (pin "10") (pinfunction "GND_10") (pintype "power_in"))
      (node (ref "IC18") (pin "10") (pinfunction "GND_10") (pintype "power_in"))
      (node (ref "IC19") (pin "10") (pinfunction "GND_10") (pintype "power_in"))
      (node (ref "IC2") (pin "10") (pinfunction "GND_10") (pintype "power_in"))
      (node (ref "IC3") (pin "10") (pinfunction "GND_10") (pintype "power_in"))
      (node (ref "IC4") (pin "10") (pinfunction "GND_10") (pintype "power_in"))
      (node (ref "IC5") (pin "10") (pinfunction "GND_10") (pintype "power_in"))
      (node (ref "IC5") (pin "12") (pinfunction "CET_12") (pintype "input"))
      (node (ref "IC6") (pin "10") (pinfunction "GND_10") (pintype "power_in"))
      (node (ref "IC7") (pin "10") (pinfunction "GND_10") (pintype "power_in"))
      (node (ref "IC8") (pin "10") (pinfunction "GND_10") (pintype "power_in"))
      (node (ref "IC9") (pin "7") (pinfunction "GND_7") (pintype "power_in"))
    )
    (net (code "58") (name "LOAD_FLAGS0") (class "Default")
      (node (ref "JP9") (pin "24") (pinfunction "24_24") (pintype "passive"))
    )
    (net (code "59") (name "LOAD_FLAGS1") (class "Default")
      (node (ref "JP9") (pin "26") (pinfunction "26_26") (pintype "passive"))
    )
    (net (code "60") (name "MDRLDINHBT") (class "Default")
      (node (ref "JP9") (pin "43") (pinfunction "43_43") (pintype "passive"))
    )
    (net (code "61") (name "MEMSEG") (class "Default")
      (node (ref "JP10") (pin "14") (pinfunction "14_14") (pintype "passive"))
    )
    (net (code "62") (name "Net-(IC1A-LOAD)") (class "Default")
      (node (ref "IC1") (pin "11") (pinfunction "LOAD_11") (pintype "input"))
      (node (ref "IC2") (pin "11") (pinfunction "LOAD_11") (pintype "input"))
      (node (ref "IC9") (pin "3") (pinfunction "O_3") (pintype "output"))
    )
    (net (code "63") (name "Net-(IC1A-RCO)") (class "Default")
      (node (ref "IC1") (pin "19") (pinfunction "RCO_19") (pintype "output"))
      (node (ref "IC2") (pin "12") (pinfunction "CET_12") (pintype "input"))
    )
    (net (code "64") (name "Net-(IC2A-RCO)") (class "Default")
      (node (ref "IC2") (pin "19") (pinfunction "RCO_19") (pintype "output"))
      (node (ref "IC3") (pin "12") (pinfunction "CET_12") (pintype "input"))
    )
    (net (code "65") (name "Net-(IC3A-LOAD)") (class "Default")
      (node (ref "IC3") (pin "11") (pinfunction "LOAD_11") (pintype "input"))
      (node (ref "IC4") (pin "11") (pinfunction "LOAD_11") (pintype "input"))
      (node (ref "IC9") (pin "6") (pinfunction "O_6") (pintype "output"))
    )
    (net (code "66") (name "Net-(IC3A-RCO)") (class "Default")
      (node (ref "IC3") (pin "19") (pinfunction "RCO_19") (pintype "output"))
      (node (ref "IC4") (pin "12") (pinfunction "CET_12") (pintype "input"))
    )
    (net (code "67") (name "Net-(IC5A-RCO)") (class "Default")
      (node (ref "IC5") (pin "19") (pinfunction "RCO_19") (pintype "output"))
      (node (ref "IC6") (pin "12") (pinfunction "CET_12") (pintype "input"))
    )
    (net (code "68") (name "Net-(IC6A-RCO)") (class "Default")
      (node (ref "IC6") (pin "19") (pinfunction "RCO_19") (pintype "output"))
      (node (ref "IC7") (pin "12") (pinfunction "CET_12") (pintype "input"))
    )
    (net (code "69") (name "Net-(IC7A-RCO)") (class "Default")
      (node (ref "IC7") (pin "19") (pinfunction "RCO_19") (pintype "output"))
      (node (ref "IC8") (pin "12") (pinfunction "CET_12") (pintype "input"))
    )
    (net (code "70") (name "Net-(IC10A-1Y)") (class "Default")
      (node (ref "IC10") (pin "4") (pinfunction "1Y_4") (pintype "output"))
      (node (ref "IC12") (pin "7") (pinfunction "CEP_7") (pintype "input"))
      (node (ref "IC13") (pin "7") (pinfunction "CEP_7") (pintype "input"))
      (node (ref "IC14") (pin "7") (pinfunction "CEP_7") (pintype "input"))
      (node (ref "IC15") (pin "7") (pinfunction "CEP_7") (pintype "input"))
    )
    (net (code "71") (name "Net-(IC10A-2Y)") (class "Default")
      (node (ref "IC10") (pin "7") (pinfunction "2Y_7") (pintype "output"))
      (node (ref "IC12") (pin "11") (pinfunction "LOAD_11") (pintype "input"))
      (node (ref "IC13") (pin "11") (pinfunction "LOAD_11") (pintype "input"))
      (node (ref "IC14") (pin "11") (pinfunction "LOAD_11") (pintype "input"))
      (node (ref "IC15") (pin "11") (pinfunction "LOAD_11") (pintype "input"))
    )
    (net (code "72") (name "Net-(IC10A-3Y)") (class "Default")
      (node (ref "IC10") (pin "9") (pinfunction "3Y_9") (pintype "output"))
      (node (ref "IC12") (pin "1") (pinfunction "U/~{D}_1") (pintype "input"))
      (node (ref "IC13") (pin "1") (pinfunction "U/~{D}_1") (pintype "input"))
      (node (ref "IC14") (pin "1") (pinfunction "U/~{D}_1") (pintype "input"))
      (node (ref "IC15") (pin "1") (pinfunction "U/~{D}_1") (pintype "input"))
    )
    (net (code "73") (name "Net-(IC10A-4Y)") (class "Default")
      (node (ref "IC10") (pin "12") (pinfunction "4Y_12") (pintype "output"))
      (node (ref "IC12") (pin "17") (pinfunction "OE_17") (pintype "input"))
      (node (ref "IC13") (pin "17") (pinfunction "OE_17") (pintype "input"))
      (node (ref "IC14") (pin "17") (pinfunction "OE_17") (pintype "input"))
      (node (ref "IC15") (pin "17") (pinfunction "OE_17") (pintype "input"))
    )
    (net (code "74") (name "Net-(IC11A-1Y)") (class "Default")
      (node (ref "IC11") (pin "4") (pinfunction "1Y_4") (pintype "output"))
      (node (ref "IC16") (pin "7") (pinfunction "CEP_7") (pintype "input"))
      (node (ref "IC17") (pin "7") (pinfunction "CEP_7") (pintype "input"))
      (node (ref "IC18") (pin "7") (pinfunction "CEP_7") (pintype "input"))
      (node (ref "IC19") (pin "7") (pinfunction "CEP_7") (pintype "input"))
    )
    (net (code "75") (name "Net-(IC11A-2Y)") (class "Default")
      (node (ref "IC11") (pin "7") (pinfunction "2Y_7") (pintype "output"))
      (node (ref "IC16") (pin "11") (pinfunction "LOAD_11") (pintype "input"))
      (node (ref "IC17") (pin "11") (pinfunction "LOAD_11") (pintype "input"))
      (node (ref "IC18") (pin "11") (pinfunction "LOAD_11") (pintype "input"))
      (node (ref "IC19") (pin "11") (pinfunction "LOAD_11") (pintype "input"))
    )
    (net (code "76") (name "Net-(IC11A-3Y)") (class "Default")
      (node (ref "IC11") (pin "9") (pinfunction "3Y_9") (pintype "output"))
      (node (ref "IC16") (pin "1") (pinfunction "U/~{D}_1") (pintype "input"))
      (node (ref "IC17") (pin "1") (pinfunction "U/~{D}_1") (pintype "input"))
      (node (ref "IC18") (pin "1") (pinfunction "U/~{D}_1") (pintype "input"))
      (node (ref "IC19") (pin "1") (pinfunction "U/~{D}_1") (pintype "input"))
    )
    (net (code "77") (name "Net-(IC11A-4Y)") (class "Default")
      (node (ref "IC11") (pin "12") (pinfunction "4Y_12") (pintype "output"))
      (node (ref "IC16") (pin "17") (pinfunction "OE_17") (pintype "input"))
      (node (ref "IC17") (pin "17") (pinfunction "OE_17") (pintype "input"))
      (node (ref "IC18") (pin "17") (pinfunction "OE_17") (pintype "input"))
      (node (ref "IC19") (pin "17") (pinfunction "OE_17") (pintype "input"))
    )
    (net (code "78") (name "Net-(IC12A-RCO)") (class "Default")
      (node (ref "IC12") (pin "19") (pinfunction "RCO_19") (pintype "output"))
      (node (ref "IC13") (pin "12") (pinfunction "CET_12") (pintype "input"))
    )
    (net (code "79") (name "Net-(IC13A-RCO)") (class "Default")
      (node (ref "IC13") (pin "19") (pinfunction "RCO_19") (pintype "output"))
      (node (ref "IC14") (pin "12") (pinfunction "CET_12") (pintype "input"))
    )
    (net (code "80") (name "Net-(IC14A-RCO)") (class "Default")
      (node (ref "IC14") (pin "19") (pinfunction "RCO_19") (pintype "output"))
      (node (ref "IC15") (pin "12") (pinfunction "CET_12") (pintype "input"))
    )
    (net (code "81") (name "Net-(IC16A-RCO)") (class "Default")
      (node (ref "IC16") (pin "19") (pinfunction "RCO_19") (pintype "output"))
      (node (ref "IC17") (pin "12") (pinfunction "CET_12") (pintype "input"))
    )
    (net (code "82") (name "Net-(IC17A-RCO)") (class "Default")
      (node (ref "IC17") (pin "19") (pinfunction "RCO_19") (pintype "output"))
      (node (ref "IC18") (pin "12") (pinfunction "CET_12") (pintype "input"))
    )
    (net (code "83") (name "Net-(IC18A-RCO)") (class "Default")
      (node (ref "IC18") (pin "19") (pinfunction "RCO_19") (pintype "output"))
      (node (ref "IC19") (pin "12") (pinfunction "CET_12") (pintype "input"))
    )
    (net (code "84") (name "PROT") (class "Default")
      (node (ref "JP10") (pin "21") (pinfunction "21_21") (pintype "passive"))
    )
    (net (code "85") (name "RST") (class "Default")
      (node (ref "JP10") (pin "9") (pinfunction "9_9") (pintype "passive"))
    )
    (net (code "86") (name "SP_DIR") (class "Default")
      (node (ref "IC10") (pin "10") (pinfunction "3B_10") (pintype "input"))
      (node (ref "IC11") (pin "11") (pinfunction "3A_11") (pintype "input"))
      (node (ref "JP10") (pin "20") (pinfunction "20_20") (pintype "passive"))
    )
    (net (code "87") (name "unconnected-(IC1A-CCO-Pad18)") (class "Default")
      (node (ref "IC1") (pin "18") (pinfunction "CCO_18") (pintype "output"))
    )
    (net (code "88") (name "unconnected-(IC2A-CCO-Pad18)") (class "Default")
      (node (ref "IC2") (pin "18") (pinfunction "CCO_18") (pintype "output"))
    )
    (net (code "89") (name "unconnected-(IC3A-CCO-Pad18)") (class "Default")
      (node (ref "IC3") (pin "18") (pinfunction "CCO_18") (pintype "output"))
    )
    (net (code "90") (name "unconnected-(IC4A-CCO-Pad18)") (class "Default")
      (node (ref "IC4") (pin "18") (pinfunction "CCO_18") (pintype "output"))
    )
    (net (code "91") (name "unconnected-(IC4A-RCO-Pad19)") (class "Default")
      (node (ref "IC4") (pin "19") (pinfunction "RCO_19") (pintype "output"))
    )
    (net (code "92") (name "unconnected-(IC5A-CCO-Pad18)") (class "Default")
      (node (ref "IC5") (pin "18") (pinfunction "CCO_18") (pintype "output"))
    )
    (net (code "93") (name "unconnected-(IC6A-CCO-Pad18)") (class "Default")
      (node (ref "IC6") (pin "18") (pinfunction "CCO_18") (pintype "output"))
    )
    (net (code "94") (name "unconnected-(IC7A-CCO-Pad18)") (class "Default")
      (node (ref "IC7") (pin "18") (pinfunction "CCO_18") (pintype "output"))
    )
    (net (code "95") (name "unconnected-(IC8A-CCO-Pad18)") (class "Default")
      (node (ref "IC8") (pin "18") (pinfunction "CCO_18") (pintype "output"))
    )
    (net (code "96") (name "unconnected-(IC8A-RCO-Pad19)") (class "Default")
      (node (ref "IC8") (pin "19") (pinfunction "RCO_19") (pintype "output"))
    )
    (net (code "97") (name "unconnected-(IC9C-O-Pad8)") (class "Default")
      (node (ref "IC9") (pin "8") (pinfunction "O_8") (pintype "output"))
    )
    (net (code "98") (name "unconnected-(IC9D-O-Pad11)") (class "Default")
      (node (ref "IC9") (pin "11") (pinfunction "O_11") (pintype "output"))
    )
    (net (code "99") (name "unconnected-(IC12A-CCO-Pad18)") (class "Default")
      (node (ref "IC12") (pin "18") (pinfunction "CCO_18") (pintype "output"))
    )
    (net (code "100") (name "unconnected-(IC13A-CCO-Pad18)") (class "Default")
      (node (ref "IC13") (pin "18") (pinfunction "CCO_18") (pintype "output"))
    )
    (net (code "101") (name "unconnected-(IC14A-CCO-Pad18)") (class "Default")
      (node (ref "IC14") (pin "18") (pinfunction "CCO_18") (pintype "output"))
    )
    (net (code "102") (name "unconnected-(IC15A-CCO-Pad18)") (class "Default")
      (node (ref "IC15") (pin "18") (pinfunction "CCO_18") (pintype "output"))
    )
    (net (code "103") (name "unconnected-(IC15A-RCO-Pad19)") (class "Default")
      (node (ref "IC15") (pin "19") (pinfunction "RCO_19") (pintype "output"))
    )
    (net (code "104") (name "unconnected-(IC16A-CCO-Pad18)") (class "Default")
      (node (ref "IC16") (pin "18") (pinfunction "CCO_18") (pintype "output"))
    )
    (net (code "105") (name "unconnected-(IC17A-CCO-Pad18)") (class "Default")
      (node (ref "IC17") (pin "18") (pinfunction "CCO_18") (pintype "output"))
    )
    (net (code "106") (name "unconnected-(IC18A-CCO-Pad18)") (class "Default")
      (node (ref "IC18") (pin "18") (pinfunction "CCO_18") (pintype "output"))
    )
    (net (code "107") (name "unconnected-(IC19A-CCO-Pad18)") (class "Default")
      (node (ref "IC19") (pin "18") (pinfunction "CCO_18") (pintype "output"))
    )
    (net (code "108") (name "unconnected-(IC19A-RCO-Pad19)") (class "Default")
      (node (ref "IC19") (pin "19") (pinfunction "RCO_19") (pintype "output"))
    )
    (net (code "109") (name "unconnected-(JP9-Pad15)") (class "Default")
      (node (ref "JP9") (pin "15") (pinfunction "15_15") (pintype "passive"))
    )
    (net (code "110") (name "unconnected-(JP9-Pad28)") (class "Default")
      (node (ref "JP9") (pin "28") (pinfunction "28_28") (pintype "passive"))
    )
    (net (code "111") (name "unconnected-(JP9-Pad30)") (class "Default")
      (node (ref "JP9") (pin "30") (pinfunction "30_30") (pintype "passive"))
    )
    (net (code "112") (name "{slash}ALUCARRYIN") (class "Default")
      (node (ref "JP9") (pin "2") (pinfunction "2_2") (pintype "passive"))
    )
    (net (code "113") (name "{slash}ALUHI2MEM") (class "Default")
      (node (ref "JP10") (pin "25") (pinfunction "25_25") (pintype "passive"))
    )
    (net (code "114") (name "{slash}ALULO2MEM") (class "Default")
      (node (ref "JP10") (pin "29") (pinfunction "29_29") (pintype "passive"))
    )
    (net (code "115") (name "{slash}ALUSHR") (class "Default")
      (node (ref "JP9") (pin "1") (pinfunction "1_1") (pintype "passive"))
    )
    (net (code "116") (name "{slash}BUSIFCEN") (class "Default")
      (node (ref "JP10") (pin "5") (pinfunction "5_5") (pintype "passive"))
    )
    (net (code "117") (name "{slash}CARRY1") (class "Default")
      (node (ref "JP9") (pin "29") (pinfunction "29_29") (pintype "passive"))
    )
    (net (code "118") (name "{slash}CARRY3") (class "Default")
      (node (ref "JP9") (pin "31") (pinfunction "31_31") (pintype "passive"))
    )
    (net (code "119") (name "{slash}CNTSP") (class "Default")
      (node (ref "IC10") (pin "3") (pinfunction "1B_3") (pintype "input"))
      (node (ref "IC11") (pin "2") (pinfunction "1A_2") (pintype "input"))
      (node (ref "JP10") (pin "3") (pinfunction "3_3") (pintype "passive"))
    )
    (net (code "120") (name "{slash}ENA") (class "Default")
      (node (ref "JP9") (pin "33") (pinfunction "33_33") (pintype "passive"))
    )
    (net (code "121") (name "{slash}ENABUS") (class "Default")
      (node (ref "JP10") (pin "22") (pinfunction "22_22") (pintype "passive"))
    )
    (net (code "122") (name "{slash}ENALU") (class "Default")
      (node (ref "JP9") (pin "39") (pinfunction "39_39") (pintype "passive"))
    )
    (net (code "123") (name "{slash}ENDP") (class "Default")
      (node (ref "JP9") (pin "44") (pinfunction "44_44") (pintype "passive"))
    )
    (net (code "124") (name "{slash}ENIPTR") (class "Default")
      (node (ref "JP9") (pin "38") (pinfunction "38_38") (pintype "passive"))
    )
    (net (code "125") (name "{slash}ENLMDR") (class "Default")
      (node (ref "JP9") (pin "34") (pinfunction "34_34") (pintype "passive"))
    )
    (net (code "126") (name "{slash}ENMAR") (class "Default")
      (node (ref "IC1") (pin "17") (pinfunction "OE_17") (pintype "input"))
      (node (ref "IC2") (pin "17") (pinfunction "OE_17") (pintype "input"))
      (node (ref "IC3") (pin "17") (pinfunction "OE_17") (pintype "input"))
      (node (ref "IC4") (pin "17") (pinfunction "OE_17") (pintype "input"))
      (node (ref "JP9") (pin "48") (pinfunction "48_48") (pintype "passive"))
    )
    (net (code "127") (name "{slash}ENMEM") (class "Default")
      (node (ref "JP10") (pin "16") (pinfunction "16_16") (pintype "passive"))
    )
    (net (code "128") (name "{slash}ENMSW") (class "Default")
      (node (ref "JP9") (pin "40") (pinfunction "40_40") (pintype "passive"))
    )
    (net (code "129") (name "{slash}ENPC") (class "Default")
      (node (ref "IC5") (pin "17") (pinfunction "OE_17") (pintype "input"))
      (node (ref "IC6") (pin "17") (pinfunction "OE_17") (pintype "input"))
      (node (ref "IC7") (pin "17") (pinfunction "OE_17") (pintype "input"))
      (node (ref "IC8") (pin "17") (pinfunction "OE_17") (pintype "input"))
      (node (ref "JP9") (pin "42") (pinfunction "42_42") (pintype "passive"))
    )
    (net (code "130") (name "{slash}ENPPC") (class "Default")
      (node (ref "JP9") (pin "37") (pinfunction "37_37") (pintype "passive"))
    )
    (net (code "131") (name "{slash}ENRMDR") (class "Default")
      (node (ref "JP9") (pin "41") (pinfunction "41_41") (pintype "passive"))
    )
    (net (code "132") (name "{slash}ENSP") (class "Default")
      (node (ref "IC10") (pin "13") (pinfunction "4B_13") (pintype "input"))
      (node (ref "IC11") (pin "14") (pinfunction "4A_14") (pintype "input"))
      (node (ref "JP9") (pin "46") (pinfunction "46_46") (pintype "passive"))
    )
    (net (code "133") (name "{slash}ENX") (class "Default")
      (node (ref "JP9") (pin "36") (pinfunction "36_36") (pintype "passive"))
    )
    (net (code "134") (name "{slash}ENY") (class "Default")
      (node (ref "JP9") (pin "35") (pinfunction "35_35") (pintype "passive"))
    )
    (net (code "135") (name "{slash}FI") (class "Default")
      (node (ref "JP10") (pin "32") (pinfunction "32_32") (pintype "passive"))
    )
    (net (code "136") (name "{slash}FS") (class "Default")
      (node (ref "IC10") (pin "1") (pinfunction "~{A}/B_1") (pintype "input"))
      (node (ref "IC11") (pin "1") (pinfunction "~{A}/B_1") (pintype "input"))
      (node (ref "JP10") (pin "30") (pinfunction "30_30") (pintype "passive"))
    )
    (net (code "137") (name "{slash}INCPC") (class "Default")
      (node (ref "IC5") (pin "7") (pinfunction "CEP_7") (pintype "input"))
      (node (ref "IC6") (pin "7") (pinfunction "CEP_7") (pintype "input"))
      (node (ref "IC7") (pin "7") (pinfunction "CEP_7") (pintype "input"))
      (node (ref "IC8") (pin "7") (pinfunction "CEP_7") (pintype "input"))
      (node (ref "JP10") (pin "1") (pinfunction "1_1") (pintype "passive"))
    )
    (net (code "138") (name "{slash}INC_MAR") (class "Default")
      (node (ref "IC1") (pin "7") (pinfunction "CEP_7") (pintype "input"))
      (node (ref "IC2") (pin "7") (pinfunction "CEP_7") (pintype "input"))
      (node (ref "IC3") (pin "7") (pinfunction "CEP_7") (pintype "input"))
      (node (ref "IC4") (pin "7") (pinfunction "CEP_7") (pintype "input"))
      (node (ref "JP9") (pin "32") (pinfunction "32_32") (pintype "passive"))
    )
    (net (code "139") (name "{slash}LATCHFLAGS") (class "Default")
      (node (ref "JP10") (pin "12") (pinfunction "12_12") (pintype "passive"))
    )
    (net (code "140") (name "{slash}LATCH_I") (class "Default")
      (node (ref "JP9") (pin "47") (pinfunction "47_47") (pintype "passive"))
    )
    (net (code "141") (name "{slash}LATCH_S") (class "Default")
      (node (ref "JP9") (pin "45") (pinfunction "45_45") (pintype "passive"))
    )
    (net (code "142") (name "{slash}LDA") (class "Default")
      (node (ref "JP9") (pin "14") (pinfunction "14_14") (pintype "passive"))
    )
    (net (code "143") (name "{slash}LDAHI") (class "Default")
      (node (ref "JP9") (pin "11") (pinfunction "11_11") (pintype "passive"))
    )
    (net (code "144") (name "{slash}LDALO") (class "Default")
      (node (ref "JP9") (pin "12") (pinfunction "12_12") (pintype "passive"))
    )
    (net (code "145") (name "{slash}LDDP") (class "Default")
      (node (ref "JP9") (pin "22") (pinfunction "22_22") (pintype "passive"))
    )
    (net (code "146") (name "{slash}LDMAR") (class "Default")
      (node (ref "IC9") (pin "1") (pinfunction "I0_1") (pintype "input"))
      (node (ref "IC9") (pin "4") (pinfunction "I0_4") (pintype "input"))
      (node (ref "JP9") (pin "23") (pinfunction "23_23") (pintype "passive"))
    )
    (net (code "147") (name "{slash}LDMARHI") (class "Default")
      (node (ref "IC9") (pin "5") (pinfunction "I1_5") (pintype "input"))
      (node (ref "JP9") (pin "17") (pinfunction "17_17") (pintype "passive"))
    )
    (net (code "148") (name "{slash}LDMARLO") (class "Default")
      (node (ref "IC9") (pin "2") (pinfunction "I1_2") (pintype "input"))
      (node (ref "JP9") (pin "18") (pinfunction "18_18") (pintype "passive"))
    )
    (net (code "149") (name "{slash}LDMDR") (class "Default")
      (node (ref "JP9") (pin "9") (pinfunction "9_9") (pintype "passive"))
    )
    (net (code "150") (name "{slash}LDMDRHI") (class "Default")
      (node (ref "JP9") (pin "10") (pinfunction "10_10") (pintype "passive"))
    )
    (net (code "151") (name "{slash}LDMDRLO") (class "Default")
      (node (ref "JP9") (pin "7") (pinfunction "7_7") (pintype "passive"))
    )
    (net (code "152") (name "{slash}LDMEM") (class "Default")
      (node (ref "JP10") (pin "15") (pinfunction "15_15") (pintype "passive"))
    )
    (net (code "153") (name "{slash}LDMSW") (class "Default")
      (node (ref "JP9") (pin "20") (pinfunction "20_20") (pintype "passive"))
    )
    (net (code "154") (name "{slash}LDPC") (class "Default")
      (node (ref "IC5") (pin "11") (pinfunction "LOAD_11") (pintype "input"))
      (node (ref "IC6") (pin "11") (pinfunction "LOAD_11") (pintype "input"))
      (node (ref "IC7") (pin "11") (pinfunction "LOAD_11") (pintype "input"))
      (node (ref "IC8") (pin "11") (pinfunction "LOAD_11") (pintype "input"))
      (node (ref "JP9") (pin "19") (pinfunction "19_19") (pintype "passive"))
    )
    (net (code "155") (name "{slash}LDPPC") (class "Default")
      (node (ref "JP10") (pin "11") (pinfunction "11_11") (pintype "passive"))
    )
    (net (code "156") (name "{slash}LDSP") (class "Default")
      (node (ref "IC10") (pin "6") (pinfunction "2B_6") (pintype "input"))
      (node (ref "IC11") (pin "5") (pinfunction "2A_5") (pintype "input"))
      (node (ref "JP9") (pin "21") (pinfunction "21_21") (pintype "passive"))
    )
    (net (code "157") (name "{slash}LDX") (class "Default")
      (node (ref "JP9") (pin "13") (pinfunction "13_13") (pintype "passive"))
    )
    (net (code "158") (name "{slash}LDY") (class "Default")
      (node (ref "JP9") (pin "16") (pinfunction "16_16") (pintype "passive"))
    )
    (net (code "159") (name "{slash}LOAD_IR") (class "Default")
      (node (ref "JP10") (pin "26") (pinfunction "26_26") (pintype "passive"))
    )
    (net (code "160") (name "{slash}MEM2ALUHI") (class "Default")
      (node (ref "JP10") (pin "27") (pinfunction "27_27") (pintype "passive"))
    )
    (net (code "161") (name "{slash}MEM2ALULO") (class "Default")
      (node (ref "JP10") (pin "31") (pinfunction "31_31") (pintype "passive"))
    )
    (net (code "162") (name "{slash}RST") (class "Default")
      (node (ref "IC5") (pin "9") (pinfunction "SCLR_9") (pintype "input"))
      (node (ref "IC6") (pin "9") (pinfunction "SCLR_9") (pintype "input"))
      (node (ref "IC7") (pin "9") (pinfunction "SCLR_9") (pintype "input"))
      (node (ref "IC8") (pin "9") (pinfunction "SCLR_9") (pintype "input"))
      (node (ref "JP10") (pin "7") (pinfunction "7_7") (pintype "passive"))
    )
  )
)
